# Sheet1.net
KiCad netlist of a schematic drawn in Altium Designer
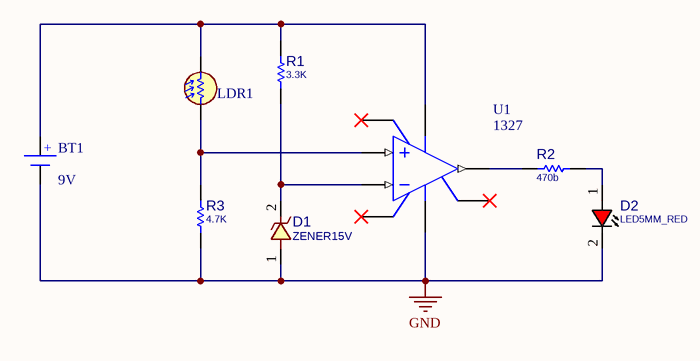
[diagram p0: Sheet1.SchDoc]

(export (version "E")
  (design (tool "Eeschema 10.0.6"))
  (components
    (comp (ref "BT1")
      (value "9V")
      (footprint "XH02_Batt")
      (description "Multicell Battery")
      (fields (field (name "VALIDATION") "NT"))
      (libsource (lib "aKaReZa") (part "Other_Elec_Battery"))
    )
    (comp (ref "D1")
      (value "ZENER15V")
      (footprint "D_AX04_DO41")
      (description "DIODE, ZENER, 0.2W, 15V")
      (fields (field (name "MANF") "Diodes"))
      (libsource (lib "Chila_PCB") (part "DIODE_THD_ZENER"))
    )
    (comp (ref "D2")
      (value "LED5MM_RED")
      (footprint "LED5MM_RED")
      (description "LED, THD, 5MM, RED")
      (fields (field (name "MANF") "MANF") (field (name "MANF_P#") "MANF_PART#"))
      (libsource (lib "Chila_PCB") (part "LED_THD_5MM_RED"))
    )
    (comp (ref "LDR1")
      (value "PhotoCell")
      (footprint "PhotoCell")
      (description "Photo Cell- Variable Resistor With Light")
      (libsource (lib "Chila_PCB") (part "LDR"))
    )
    (comp (ref "R1")
      (value "3.3K")
      (footprint "R025W_AX04")
      (description "RESISTOR, THD")
      (fields (field (name "MANF_P#") "RK73H1ETTP4701F") (field (name "MANF") "KOA SPEER"))
      (libsource (lib "Chila_PCB") (part "RES_THD"))
    )
    (comp (ref "R2")
      (value "470b")
      (footprint "R025W_AX04")
      (description "RESISTOR, THD")
      (fields (field (name "MANF_P#") "RK73H1ETTP4701F") (field (name "MANF") "KOA SPEER"))
      (libsource (lib "Chila_PCB") (part "RES_THD"))
    )
    (comp (ref "R3")
      (value "4.7K")
      (footprint "R025W_AX04")
      (description "RESISTOR, THD")
      (fields (field (name "MANF_P#") "RK73H1ETTP4701F") (field (name "MANF") "KOA SPEER"))
      (libsource (lib "Chila_PCB") (part "RES_THD"))
    )
    (comp (ref "U1")
      (value "LM741")
      (footprint "CDIP8")
      (description "Low offset, low drift JFET input operational amplifie")
      (fields (field (name "INFLOW") "1327") (field (name "VALIDATION") "NT"))
      (libsource (lib "aKaReZa") (part "IC_Opamp_LF411CN"))
    )
  )
  (nets
    (net (code "1") (name "GND") (class "Default")
      (node (ref "BT1") (pin "2") (pinfunction "-_2") (pintype "passive"))
      (node (ref "D1") (pin "1") (pinfunction "1_1") (pintype "passive"))
      (node (ref "D2") (pin "2") (pinfunction "CATHODE_2") (pintype "passive"))
      (node (ref "R3") (pin "1") (pinfunction "1_1") (pintype "passive"))
      (node (ref "U1") (pin "4") (pinfunction "V-_4") (pintype "power_in"))
    )
    (net (code "2") (name "Net-(BT1-+)") (class "Default")
      (node (ref "BT1") (pin "1") (pinfunction "+_1") (pintype "passive"))
      (node (ref "LDR1") (pin "2") (pinfunction "2_2") (pintype "passive"))
      (node (ref "R1") (pin "2") (pinfunction "2_2") (pintype "passive"))
      (node (ref "U1") (pin "7") (pinfunction "V+_7") (pintype "power_in"))
    )
    (net (code "3") (name "Net-(D2-ANODE)") (class "Default")
      (node (ref "D2") (pin "1") (pinfunction "ANODE_1") (pintype "passive"))
      (node (ref "R2") (pin "1") (pinfunction "1_1") (pintype "passive"))
    )
    (net (code "4") (name "Net-(U1-IN+)") (class "Default")
      (node (ref "LDR1") (pin "1") (pinfunction "1_1") (pintype "passive"))
      (node (ref "R3") (pin "2") (pinfunction "2_2") (pintype "passive"))
      (node (ref "U1") (pin "3") (pinfunction "IN+_3") (pintype "input"))
    )
    (net (code "5") (name "Net-(U1-IN-)") (class "Default")
      (node (ref "D1") (pin "2") (pinfunction "2_2") (pintype "passive"))
      (node (ref "R1") (pin "1") (pinfunction "1_1") (pintype "passive"))
      (node (ref "U1") (pin "2") (pinfunction "IN-_2") (pintype "input"))
    )
    (net (code "6") (name "Net-(U1-OUT)") (class "Default")
      (node (ref "R2") (pin "2") (pinfunction "2_2") (pintype "passive"))
      (node (ref "U1") (pin "6") (pinfunction "OUT_6") (pintype "output"))
    )
    (net (code "7") (name "unconnected-(U1-BAL-Pad1)") (class "Default")
      (node (ref "U1") (pin "1") (pinfunction "BAL_1") (pintype "passive+no_connect"))
    )
    (net (code "8") (name "unconnected-(U1-BAL-Pad5)") (class "Default")
      (node (ref "U1") (pin "5") (pinfunction "BAL_5") (pintype "passive+no_connect"))
    )
    (net (code "9") (name "unconnected-(U1-NC-Pad8)") (class "Default")
      (node (ref "U1") (pin "8") (pinfunction "NC_8") (pintype "passive+no_connect"))
    )
  )
)
